# 12-bit-asm.net
KiCad netlist of a schematic drawn in EAGLE
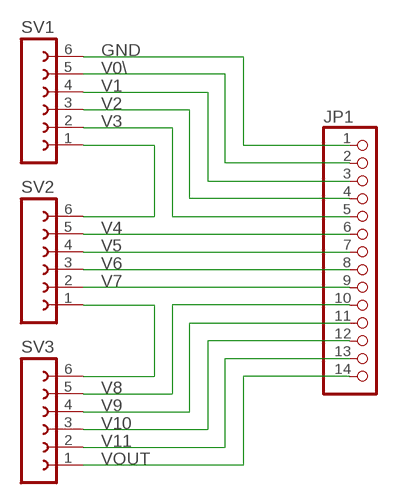
[diagram p0: schematic, sheet 1]

(export (version "E")
  (design (tool "Eeschema 10.0.6"))
  (components
    (comp (ref "JP1")
      (value "PINHD-1X14")
      (footprint "eagle-import:1X14")
      (libsource (lib "eagle-import") (part "PINHD-1X14"))
    )
    (comp (ref "SV1")
      (value "FE06-1")
      (footprint "eagle-import:FE06")
      (libsource (lib "eagle-import") (part "FE06-1"))
    )
    (comp (ref "SV2")
      (value "FE06-1")
      (footprint "eagle-import:FE06")
      (libsource (lib "eagle-import") (part "FE06-1"))
    )
    (comp (ref "SV3")
      (value "FE06-1")
      (footprint "eagle-import:FE06")
      (libsource (lib "eagle-import") (part "FE06-1"))
    )
  )
  (nets
    (net (code "1") (name "/GND") (class "Default")
      (node (ref "JP1") (pin "1") (pinfunction "1_1") (pintype "passive"))
      (node (ref "SV1") (pin "6") (pinfunction "6_6") (pintype "passive"))
    )
    (net (code "2") (name "/V0\\") (class "Default")
      (node (ref "JP1") (pin "2") (pinfunction "2_2") (pintype "passive"))
      (node (ref "SV1") (pin "5") (pinfunction "5_5") (pintype "passive"))
    )
    (net (code "3") (name "/V1") (class "Default")
      (node (ref "JP1") (pin "3") (pinfunction "3_3") (pintype "passive"))
      (node (ref "SV1") (pin "4") (pinfunction "4_4") (pintype "passive"))
    )
    (net (code "4") (name "/V2") (class "Default")
      (node (ref "JP1") (pin "4") (pinfunction "4_4") (pintype "passive"))
      (node (ref "SV1") (pin "3") (pinfunction "3_3") (pintype "passive"))
    )
    (net (code "5") (name "/V3") (class "Default")
      (node (ref "JP1") (pin "5") (pinfunction "5_5") (pintype "passive"))
      (node (ref "SV1") (pin "2") (pinfunction "2_2") (pintype "passive"))
    )
    (net (code "6") (name "/V4") (class "Default")
      (node (ref "JP1") (pin "6") (pinfunction "6_6") (pintype "passive"))
      (node (ref "SV2") (pin "5") (pinfunction "5_5") (pintype "passive"))
    )
    (net (code "7") (name "/V5") (class "Default")
      (node (ref "JP1") (pin "7") (pinfunction "7_7") (pintype "passive"))
      (node (ref "SV2") (pin "4") (pinfunction "4_4") (pintype "passive"))
    )
    (net (code "8") (name "/V6") (class "Default")
      (node (ref "JP1") (pin "8") (pinfunction "8_8") (pintype "passive"))
      (node (ref "SV2") (pin "3") (pinfunction "3_3") (pintype "passive"))
    )
    (net (code "9") (name "/V7") (class "Default")
      (node (ref "JP1") (pin "9") (pinfunction "9_9") (pintype "passive"))
      (node (ref "SV2") (pin "2") (pinfunction "2_2") (pintype "passive"))
    )
    (net (code "10") (name "/V8") (class "Default")
      (node (ref "JP1") (pin "10") (pinfunction "10_10") (pintype "passive"))
      (node (ref "SV3") (pin "5") (pinfunction "5_5") (pintype "passive"))
    )
    (net (code "11") (name "/V9") (class "Default")
      (node (ref "JP1") (pin "11") (pinfunction "11_11") (pintype "passive"))
      (node (ref "SV3") (pin "4") (pinfunction "4_4") (pintype "passive"))
    )
    (net (code "12") (name "/V10") (class "Default")
      (node (ref "JP1") (pin "12") (pinfunction "12_12") (pintype "passive"))
      (node (ref "SV3") (pin "3") (pinfunction "3_3") (pintype "passive"))
    )
    (net (code "13") (name "/V11") (class "Default")
      (node (ref "JP1") (pin "13") (pinfunction "13_13") (pintype "passive"))
      (node (ref "SV3") (pin "2") (pinfunction "2_2") (pintype "passive"))
    )
    (net (code "14") (name "/VOUT") (class "Default")
      (node (ref "JP1") (pin "14") (pinfunction "14_14") (pintype "passive"))
      (node (ref "SV3") (pin "1") (pinfunction "1_1") (pintype "passive"))
    )
    (net (code "15") (name "Net-(SV1-Pad1)") (class "Default")
      (node (ref "SV1") (pin "1") (pinfunction "1_1") (pintype "passive"))
      (node (ref "SV2") (pin "6") (pinfunction "6_6") (pintype "passive"))
    )
    (net (code "16") (name "Net-(SV2-Pad1)") (class "Default")
      (node (ref "SV2") (pin "1") (pinfunction "1_1") (pintype "passive"))
      (node (ref "SV3") (pin "6") (pinfunction "6_6") (pintype "passive"))
    )
  )
)
